# Phase_Current_Voltage_Sense.net
KiCad netlist of a schematic drawn in Altium Designer
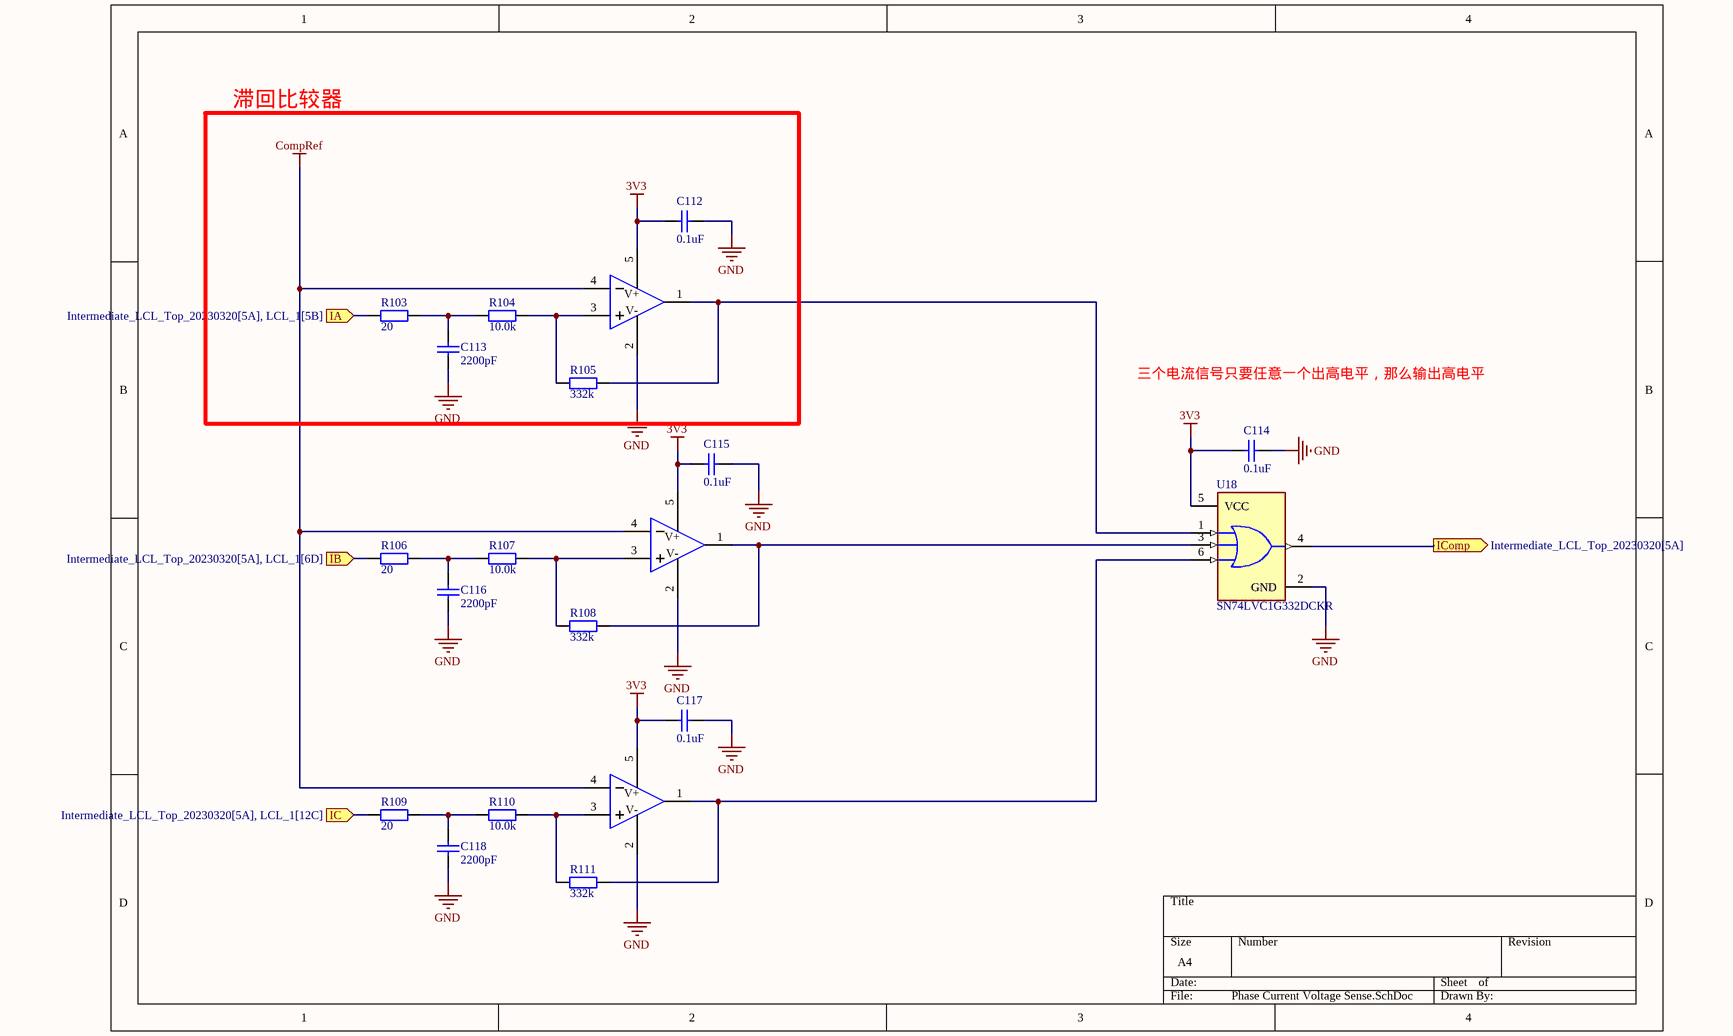
[diagram p0: Phase Current Voltage Sense.SchDoc]

(export (version "E")
  (design (tool "Eeschema 10.0.6"))
  (components
    (comp (ref "C112")
      (value "0.1uF")
      (footprint "CAPC1608X06N")
      (description "Capacitor")
      (fields (field (name "PUBLISHER") "Altium Limited"))
      (libsource (lib "Simscale") (part "Cap"))
    )
    (comp (ref "C113")
      (value "2200pF")
      (footprint "CAPC1608X06N")
      (description "Capacitor")
      (fields (field (name "PUBLISHER") "Altium Limited"))
      (libsource (lib "Simscale") (part "Cap"))
    )
    (comp (ref "C114")
      (value "0.1uF")
      (footprint "CAPC1608X06N")
      (description "Capacitor")
      (fields (field (name "PUBLISHER") "Altium Limited"))
      (libsource (lib "Simscale") (part "Cap"))
    )
    (comp (ref "C115")
      (value "0.1uF")
      (footprint "CAPC1608X06N")
      (description "Capacitor")
      (fields (field (name "PUBLISHER") "Altium Limited"))
      (libsource (lib "Simscale") (part "Cap"))
    )
    (comp (ref "C116")
      (value "2200pF")
      (footprint "CAPC1608X06N")
      (description "Capacitor")
      (fields (field (name "PUBLISHER") "Altium Limited"))
      (libsource (lib "Simscale") (part "Cap"))
    )
    (comp (ref "C117")
      (value "0.1uF")
      (footprint "CAPC1608X06N")
      (description "Capacitor")
      (fields (field (name "PUBLISHER") "Altium Limited"))
      (libsource (lib "Simscale") (part "Cap"))
    )
    (comp (ref "C118")
      (value "2200pF")
      (footprint "CAPC1608X06N")
      (description "Capacitor")
      (fields (field (name "PUBLISHER") "Altium Limited"))
      (libsource (lib "Simscale") (part "Cap"))
    )
    (comp (ref "R103")
      (value "20")
      (footprint "RESC1608X05N")
      (description "贴片电阻")
      (libsource (lib "Simscale") (part "0603 100KΩ (1003) 1%_4"))
    )
    (comp (ref "R104")
      (value "10.0k")
      (footprint "RESC1608X05N")
      (description "贴片电阻")
      (libsource (lib "Simscale") (part "0603 100KΩ (1003) 1%_4"))
    )
    (comp (ref "R105")
      (value "332k")
      (footprint "RESC1608X05N")
      (description "贴片电阻")
      (libsource (lib "Simscale") (part "0603 100KΩ (1003) 1%_4"))
    )
    (comp (ref "R106")
      (value "20")
      (footprint "RESC1608X05N")
      (description "贴片电阻")
      (libsource (lib "Simscale") (part "0603 100KΩ (1003) 1%_4"))
    )
    (comp (ref "R107")
      (value "10.0k")
      (footprint "RESC1608X05N")
      (description "贴片电阻")
      (libsource (lib "Simscale") (part "0603 100KΩ (1003) 1%_4"))
    )
    (comp (ref "R108")
      (value "332k")
      (footprint "RESC1608X05N")
      (description "贴片电阻")
      (libsource (lib "Simscale") (part "0603 100KΩ (1003) 1%_4"))
    )
    (comp (ref "R109")
      (value "20")
      (footprint "RESC1608X05N")
      (description "贴片电阻")
      (libsource (lib "Simscale") (part "0603 100KΩ (1003) 1%_4"))
    )
    (comp (ref "R110")
      (value "10.0k")
      (footprint "RESC1608X05N")
      (description "贴片电阻")
      (libsource (lib "Simscale") (part "0603 100KΩ (1003) 1%_4"))
    )
    (comp (ref "R111")
      (value "332k")
      (footprint "RESC1608X05N")
      (description "贴片电阻")
      (libsource (lib "Simscale") (part "0603 100KΩ (1003) 1%_4"))
    )
    (comp (ref "U17")
      (value "TLV3201AIDBVR")
      (footprint "SOT-23-5_L3.0-W1.7-P0.95-LS2.8-BR")
      (fields (field (name "MANUFACTURER") "TI(德州仪器)"))
      (libsource (lib "TLV3201AIDBVR1_TLV3201AIDBVR.schdoc") (part "TLV3201AIDBVR"))
    )
    (comp (ref "U18")
      (value "SN74LVC1G332DCKR")
      (footprint "FP-DCK0006A-MFG")
      (description "IC GATE OR 1CH 3-INP SC70-6")
      (fields
        (field (name "MANUFACTURER") "Texas Instruments")
        (field (name "OCTOPART") "https://octopart.com/sn74lvc1g332dckr-texas+instruments-464861")
      )
      (libsource (lib "Altium Content Vault") (part "a1fbee6839145229a27344b52c53a8d"))
    )
    (comp (ref "U19")
      (value "TLV3201AIDBVR")
      (footprint "SOT-23-5_L3.0-W1.7-P0.95-LS2.8-BR")
      (fields (field (name "MANUFACTURER") "TI(德州仪器)"))
      (libsource (lib "TLV3201AIDBVR1_TLV3201AIDBVR.schdoc") (part "TLV3201AIDBVR"))
    )
    (comp (ref "U20")
      (value "TLV3201AIDBVR")
      (footprint "SOT-23-5_L3.0-W1.7-P0.95-LS2.8-BR")
      (fields (field (name "MANUFACTURER") "TI(德州仪器)"))
      (libsource (lib "TLV3201AIDBVR1_TLV3201AIDBVR.schdoc") (part "TLV3201AIDBVR"))
    )
  )
  (nets
    (net (code "1") (name "/IA") (class "Default")
      (node (ref "R103") (pin "2") (pinfunction "2_2") (pintype "passive"))
    )
    (net (code "2") (name "/IB") (class "Default")
      (node (ref "R106") (pin "2") (pinfunction "2_2") (pintype "passive"))
    )
    (net (code "3") (name "/IC") (class "Default")
      (node (ref "R109") (pin "2") (pinfunction "2_2") (pintype "passive"))
    )
    (net (code "4") (name "/IComp") (class "Default")
      (node (ref "U18") (pin "4") (pinfunction "Y_4") (pintype "output"))
    )
    (net (code "5") (name "3V3") (class "Default")
      (node (ref "C112") (pin "1") (pinfunction "1_1") (pintype "passive"))
      (node (ref "C114") (pin "1") (pinfunction "1_1") (pintype "passive"))
      (node (ref "C115") (pin "1") (pinfunction "1_1") (pintype "passive"))
      (node (ref "C117") (pin "1") (pinfunction "1_1") (pintype "passive"))
      (node (ref "U17") (pin "5") (pinfunction "VCC_5") (pintype "passive"))
      (node (ref "U18") (pin "5") (pinfunction "VCC_5") (pintype "power_in"))
      (node (ref "U19") (pin "5") (pinfunction "VCC_5") (pintype "passive"))
      (node (ref "U20") (pin "5") (pinfunction "VCC_5") (pintype "passive"))
    )
    (net (code "6") (name "CompRef") (class "Default")
      (node (ref "U17") (pin "4") (pinfunction "IN-_4") (pintype "passive"))
      (node (ref "U19") (pin "4") (pinfunction "IN-_4") (pintype "passive"))
      (node (ref "U20") (pin "4") (pinfunction "IN-_4") (pintype "passive"))
    )
    (net (code "7") (name "GND") (class "Default")
      (node (ref "C112") (pin "2") (pinfunction "2_2") (pintype "passive"))
      (node (ref "C113") (pin "2") (pinfunction "2_2") (pintype "passive"))
      (node (ref "C114") (pin "2") (pinfunction "2_2") (pintype "passive"))
      (node (ref "C115") (pin "2") (pinfunction "2_2") (pintype "passive"))
      (node (ref "C116") (pin "2") (pinfunction "2_2") (pintype "passive"))
      (node (ref "C117") (pin "2") (pinfunction "2_2") (pintype "passive"))
      (node (ref "C118") (pin "2") (pinfunction "2_2") (pintype "passive"))
      (node (ref "U17") (pin "2") (pinfunction "GND_2") (pintype "passive"))
      (node (ref "U18") (pin "2") (pinfunction "GND_2") (pintype "power_in"))
      (node (ref "U19") (pin "2") (pinfunction "GND_2") (pintype "passive"))
      (node (ref "U20") (pin "2") (pinfunction "GND_2") (pintype "passive"))
    )
    (net (code "8") (name "Net-(C113-Pad1)") (class "Default")
      (node (ref "C113") (pin "1") (pinfunction "1_1") (pintype "passive"))
      (node (ref "R103") (pin "1") (pinfunction "1_1") (pintype "passive"))
      (node (ref "R104") (pin "2") (pinfunction "2_2") (pintype "passive"))
    )
    (net (code "9") (name "Net-(C116-Pad1)") (class "Default")
      (node (ref "C116") (pin "1") (pinfunction "1_1") (pintype "passive"))
      (node (ref "R106") (pin "1") (pinfunction "1_1") (pintype "passive"))
      (node (ref "R107") (pin "2") (pinfunction "2_2") (pintype "passive"))
    )
    (net (code "10") (name "Net-(C118-Pad1)") (class "Default")
      (node (ref "C118") (pin "1") (pinfunction "1_1") (pintype "passive"))
      (node (ref "R109") (pin "1") (pinfunction "1_1") (pintype "passive"))
      (node (ref "R110") (pin "2") (pinfunction "2_2") (pintype "passive"))
    )
    (net (code "11") (name "Net-(U17-IN+)") (class "Default")
      (node (ref "R104") (pin "1") (pinfunction "1_1") (pintype "passive"))
      (node (ref "R105") (pin "2") (pinfunction "2_2") (pintype "passive"))
      (node (ref "U17") (pin "3") (pinfunction "IN+_3") (pintype "passive"))
    )
    (net (code "12") (name "Net-(U17-OUT)") (class "Default")
      (node (ref "R105") (pin "1") (pinfunction "1_1") (pintype "passive"))
      (node (ref "U17") (pin "1") (pinfunction "OUT_1") (pintype "passive"))
      (node (ref "U18") (pin "1") (pinfunction "A_1") (pintype "input"))
    )
    (net (code "13") (name "Net-(U18-B)") (class "Default")
      (node (ref "R108") (pin "1") (pinfunction "1_1") (pintype "passive"))
      (node (ref "U18") (pin "3") (pinfunction "B_3") (pintype "input"))
      (node (ref "U19") (pin "1") (pinfunction "OUT_1") (pintype "passive"))
    )
    (net (code "14") (name "Net-(U18-C)") (class "Default")
      (node (ref "R111") (pin "1") (pinfunction "1_1") (pintype "passive"))
      (node (ref "U18") (pin "6") (pinfunction "C_6") (pintype "input"))
      (node (ref "U20") (pin "1") (pinfunction "OUT_1") (pintype "passive"))
    )
    (net (code "15") (name "Net-(U19-IN+)") (class "Default")
      (node (ref "R107") (pin "1") (pinfunction "1_1") (pintype "passive"))
      (node (ref "R108") (pin "2") (pinfunction "2_2") (pintype "passive"))
      (node (ref "U19") (pin "3") (pinfunction "IN+_3") (pintype "passive"))
    )
    (net (code "16") (name "Net-(U20-IN+)") (class "Default")
      (node (ref "R110") (pin "1") (pinfunction "1_1") (pintype "passive"))
      (node (ref "R111") (pin "2") (pinfunction "2_2") (pintype "passive"))
      (node (ref "U20") (pin "3") (pinfunction "IN+_3") (pintype "passive"))
    )
  )
)
